# HW_Mechanical_Parts.net
KiCad netlist of a schematic drawn in Altium Designer
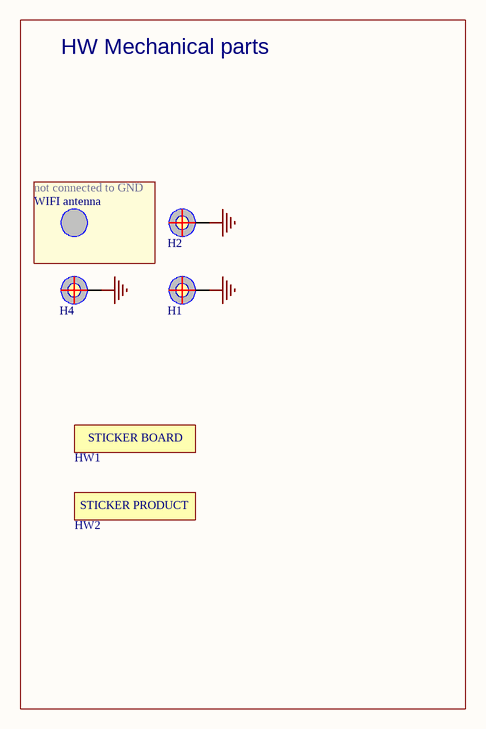
[diagram p0: HW_Mechanical_Parts.SchDoc]

(export (version "E")
  (design (tool "Eeschema 10.0.6"))
  (components
    (comp (ref "H1")
      (value "POSITION HOLE C6D3R5")
      (footprint "HOLE_C6D3R5")
      (libsource (lib "MCD_TOOLS_MISCELLANEOUS") (part "POSITION HOLE C6D3R5"))
    )
    (comp (ref "H2")
      (value "POSITION HOLE C6D3R5")
      (footprint "HOLE_C6D3R5")
      (libsource (lib "MCD_TOOLS_MISCELLANEOUS") (part "POSITION HOLE C6D3R5"))
    )
    (comp (ref "H4")
      (value "POSITION HOLE C6D3R5")
      (footprint "HOLE_C6D3R5")
      (libsource (lib "MCD_TOOLS_MISCELLANEOUS") (part "POSITION HOLE C6D3R5"))
    )
    (comp (ref "HW1") (value "STICKER_BOARD") (libsource (lib "mb1260") (part "STICKER_BOARD")))
    (comp (ref "HW2") (value "STICKER_PRODUCT") (libsource (lib "mb1260") (part "STICKER_PRODUCT")))
  )
  (nets
    (net (code "1") (name "GND") (class "Default")
      (node (ref "H1") (pin "1") (pinfunction "1_1") (pintype "passive"))
      (node (ref "H2") (pin "1") (pinfunction "1_1") (pintype "passive"))
      (node (ref "H4") (pin "1") (pinfunction "1_1") (pintype "passive"))
    )
  )
)
